# LMS.net
KiCad netlist of a schematic drawn in Altium Designer
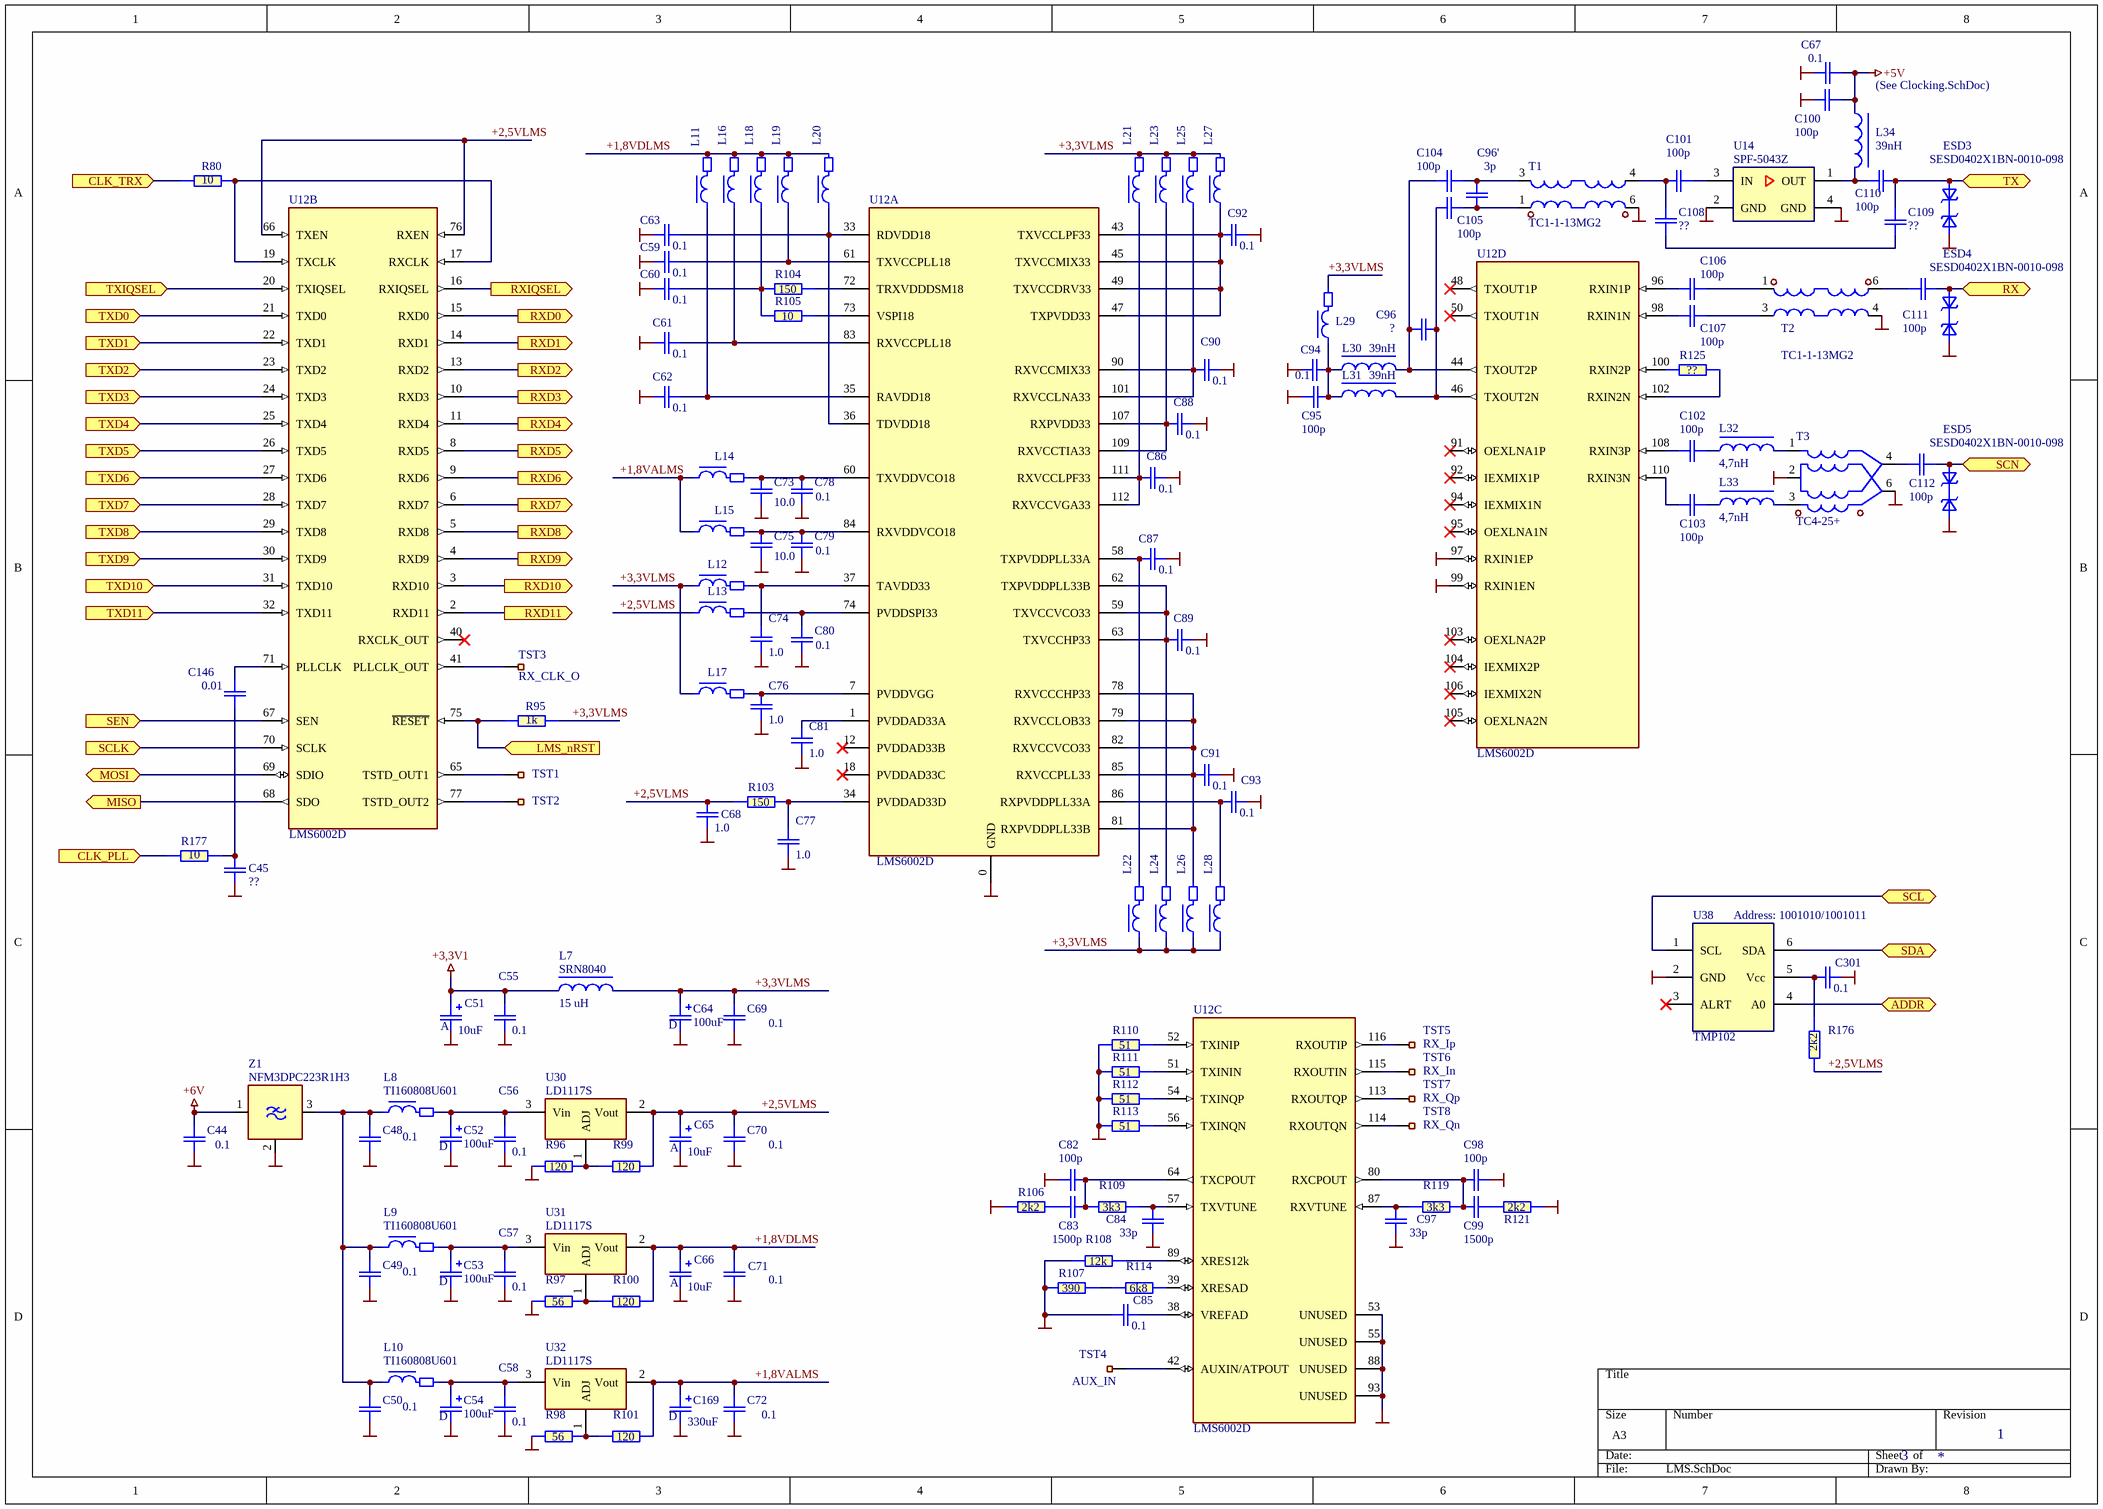
[diagram p0: LMS.SchDoc]

(export (version "E")
  (design (tool "Eeschema 10.0.6"))
  (components
    (comp (ref "C44")
      (value "0.1")
      (footprint "C0402-Phillips")
      (description "Конденсатор")
      (fields (field (name "MANUFACTURER") "MURATA") (field (name "TOLERANCE") "20%"))
      (libsource (lib "Capacitors") (part "C0402"))
    )
    (comp (ref "C45")
      (value "??")
      (footprint "C0603-PHILLIPS")
      (description "Конденсатор")
      (fields (field (name "MANUFACTURER") "MURATA") (field (name "TOLERANCE") "20%"))
      (libsource (lib "altium-import") (part "root_2_mirrored_C0603_"))
    )
    (comp (ref "C48")
      (value "0.1")
      (footprint "C0402-Phillips")
      (description "Конденсатор")
      (fields (field (name "MANUFACTURER") "MURATA") (field (name "TOLERANCE") "20%"))
      (libsource (lib "Capacitors") (part "C0402"))
    )
    (comp (ref "C49")
      (value "0.1")
      (footprint "C0402-Phillips")
      (description "Конденсатор")
      (fields (field (name "MANUFACTURER") "MURATA") (field (name "TOLERANCE") "20%"))
      (libsource (lib "Capacitors") (part "C0402"))
    )
    (comp (ref "C50")
      (value "0.1")
      (footprint "C0402-Phillips")
      (description "Конденсатор")
      (fields (field (name "MANUFACTURER") "MURATA") (field (name "TOLERANCE") "20%"))
      (libsource (lib "Capacitors") (part "C0402"))
    )
    (comp (ref "C51")
      (value "10uF")
      (footprint "CA3216")
      (description "Конденсатор")
      (fields (field (name "MANUFACTURER") "SPRAGUE"))
      (libsource (lib "Capacitors") (part "CA3216"))
    )
    (comp (ref "C52")
      (value "100uF")
      (footprint "cd7343")
      (description "Конденсатор")
      (fields (field (name "MANUFACTURER") "SPRAGUE"))
      (libsource (lib "altium-import") (part "root_0_CD7343_"))
    )
    (comp (ref "C53")
      (value "100uF")
      (footprint "cd7343")
      (description "Конденсатор")
      (fields (field (name "MANUFACTURER") "SPRAGUE"))
      (libsource (lib "altium-import") (part "root_0_CD7343_"))
    )
    (comp (ref "C54")
      (value "100uF")
      (footprint "cd7343")
      (description "Конденсатор")
      (fields (field (name "MANUFACTURER") "SPRAGUE"))
      (libsource (lib "altium-import") (part "root_0_CD7343_"))
    )
    (comp (ref "C55")
      (value "0.1")
      (footprint "C0402-Phillips")
      (description "Конденсатор")
      (fields (field (name "MANUFACTURER") "MURATA") (field (name "TOLERANCE") "20%"))
      (libsource (lib "Capacitors") (part "C0402"))
    )
    (comp (ref "C56")
      (value "0.1")
      (footprint "C0402-Phillips")
      (description "Конденсатор")
      (fields (field (name "MANUFACTURER") "MURATA") (field (name "TOLERANCE") "20%"))
      (libsource (lib "Capacitors") (part "C0402"))
    )
    (comp (ref "C57")
      (value "0.1")
      (footprint "C0402-Phillips")
      (description "Конденсатор")
      (fields (field (name "MANUFACTURER") "MURATA") (field (name "TOLERANCE") "20%"))
      (libsource (lib "Capacitors") (part "C0402"))
    )
    (comp (ref "C58")
      (value "0.1")
      (footprint "C0402-Phillips")
      (description "Конденсатор")
      (fields (field (name "MANUFACTURER") "MURATA") (field (name "TOLERANCE") "20%"))
      (libsource (lib "Capacitors") (part "C0402"))
    )
    (comp (ref "C59")
      (value "0.1")
      (footprint "C0402-Phillips")
      (description "Конденсатор")
      (fields (field (name "MANUFACTURER") "MURATA") (field (name "TOLERANCE") "20%"))
      (libsource (lib "Capacitors") (part "C0402"))
    )
    (comp (ref "C60")
      (value "0.1")
      (footprint "C0402-Phillips")
      (description "Конденсатор")
      (fields (field (name "MANUFACTURER") "MURATA") (field (name "TOLERANCE") "20%"))
      (libsource (lib "Capacitors") (part "C0402"))
    )
    (comp (ref "C61")
      (value "0.1")
      (footprint "C0402-Phillips")
      (description "Конденсатор")
      (fields (field (name "MANUFACTURER") "MURATA") (field (name "TOLERANCE") "20%"))
      (libsource (lib "Capacitors") (part "C0402"))
    )
    (comp (ref "C62")
      (value "0.1")
      (footprint "C0402-Phillips")
      (description "Конденсатор")
      (fields (field (name "MANUFACTURER") "MURATA") (field (name "TOLERANCE") "20%"))
      (libsource (lib "Capacitors") (part "C0402"))
    )
    (comp (ref "C63")
      (value "0.1")
      (footprint "C0402-Phillips")
      (description "Конденсатор")
      (fields (field (name "MANUFACTURER") "MURATA") (field (name "TOLERANCE") "20%"))
      (libsource (lib "Capacitors") (part "C0402"))
    )
    (comp (ref "C64")
      (value "100uF")
      (footprint "cd7343")
      (description "Конденсатор")
      (fields (field (name "MANUFACTURER") "SPRAGUE"))
      (libsource (lib "altium-import") (part "root_0_CD7343_"))
    )
    (comp (ref "C65")
      (value "10uF")
      (footprint "CA3216")
      (description "Конденсатор")
      (fields (field (name "MANUFACTURER") "SPRAGUE"))
      (libsource (lib "Capacitors") (part "CA3216"))
    )
    (comp (ref "C66")
      (value "10uF")
      (footprint "CA3216")
      (description "Конденсатор")
      (fields (field (name "MANUFACTURER") "SPRAGUE"))
      (libsource (lib "Capacitors") (part "CA3216"))
    )
    (comp (ref "C67")
      (value "0.1")
      (footprint "C0402-Phillips")
      (description "Конденсатор")
      (fields (field (name "MANUFACTURER") "MURATA") (field (name "TOLERANCE") "20%"))
      (libsource (lib "Capacitors") (part "C0402"))
    )
    (comp (ref "C68")
      (value "1.0")
      (footprint "C0603-PHILLIPS")
      (description "Конденсатор")
      (fields (field (name "MANUFACTURER") "MURATA") (field (name "TOLERANCE") "20%"))
      (libsource (lib "altium-import") (part "root_0_C0603_"))
    )
    (comp (ref "C69")
      (value "0.1")
      (footprint "C0402-Phillips")
      (description "Конденсатор")
      (fields (field (name "MANUFACTURER") "MURATA") (field (name "TOLERANCE") "20%"))
      (libsource (lib "Capacitors") (part "C0402"))
    )
    (comp (ref "C70")
      (value "0.1")
      (footprint "C0402-Phillips")
      (description "Конденсатор")
      (fields (field (name "MANUFACTURER") "MURATA") (field (name "TOLERANCE") "20%"))
      (libsource (lib "Capacitors") (part "C0402"))
    )
    (comp (ref "C71")
      (value "0.1")
      (footprint "C0402-Phillips")
      (description "Конденсатор")
      (fields (field (name "MANUFACTURER") "MURATA") (field (name "TOLERANCE") "20%"))
      (libsource (lib "Capacitors") (part "C0402"))
    )
    (comp (ref "C72")
      (value "0.1")
      (footprint "C0402-Phillips")
      (description "Конденсатор")
      (fields (field (name "MANUFACTURER") "MURATA") (field (name "TOLERANCE") "20%"))
      (libsource (lib "Capacitors") (part "C0402"))
    )
    (comp (ref "C73")
      (value "10.0")
      (footprint "C0603-Phillips")
      (description "Конденсатор")
      (fields (field (name "MANUFACTURER") "MURATA") (field (name "TOLERANCE") "20%"))
      (libsource (lib "Capacitors") (part "C0603"))
    )
    (comp (ref "C74")
      (value "1.0")
      (footprint "C0603-PHILLIPS")
      (description "Конденсатор")
      (fields (field (name "MANUFACTURER") "MURATA") (field (name "TOLERANCE") "20%"))
      (libsource (lib "altium-import") (part "root_0_C0603_"))
    )
    (comp (ref "C75")
      (value "10.0")
      (footprint "C0603-Phillips")
      (description "Конденсатор")
      (fields (field (name "MANUFACTURER") "MURATA") (field (name "TOLERANCE") "20%"))
      (libsource (lib "Capacitors") (part "C0603"))
    )
    (comp (ref "C76")
      (value "1.0")
      (footprint "C0603-PHILLIPS")
      (description "Конденсатор")
      (fields (field (name "MANUFACTURER") "MURATA") (field (name "TOLERANCE") "20%"))
      (libsource (lib "altium-import") (part "root_0_C0603_"))
    )
    (comp (ref "C77")
      (value "1.0")
      (footprint "C0603-PHILLIPS")
      (description "Конденсатор")
      (fields (field (name "MANUFACTURER") "MURATA") (field (name "TOLERANCE") "20%"))
      (libsource (lib "altium-import") (part "root_0_C0603_"))
    )
    (comp (ref "C78")
      (value "0.1")
      (footprint "C0402-Phillips")
      (description "Конденсатор")
      (fields (field (name "MANUFACTURER") "MURATA") (field (name "TOLERANCE") "20%"))
      (libsource (lib "Capacitors") (part "C0402"))
    )
    (comp (ref "C79")
      (value "0.1")
      (footprint "C0402-cirq")
      (description "Конденсатор")
      (fields (field (name "MANUFACTURER") "MURATA") (field (name "TOLERANCE") "20%"))
      (libsource (lib "Capacitors") (part "C0402"))
    )
    (comp (ref "C80")
      (value "0.1")
      (footprint "C0402-cirq")
      (description "Конденсатор")
      (fields (field (name "MANUFACTURER") "MURATA") (field (name "TOLERANCE") "20%"))
      (libsource (lib "Capacitors") (part "C0402"))
    )
    (comp (ref "C81")
      (value "1.0")
      (footprint "C0603-PHILLIPS")
      (description "Конденсатор")
      (fields (field (name "MANUFACTURER") "MURATA") (field (name "TOLERANCE") "20%"))
      (libsource (lib "altium-import") (part "root_0_C0603_"))
    )
    (comp (ref "C82")
      (value "100p")
      (footprint "C0603-PHILLIPS")
      (description "Конденсатор")
      (fields (field (name "MANUFACTURER") "MURATA") (field (name "TOLERANCE") "20%"))
      (libsource (lib "altium-import") (part "root_1_mirrored_C0603_"))
    )
    (comp (ref "C83")
      (value "1500p")
      (footprint "C0603-PHILLIPS")
      (description "Конденсатор")
      (fields (field (name "MANUFACTURER") "MURATA") (field (name "TOLERANCE") "20%"))
      (libsource (lib "altium-import") (part "root_1_mirrored_C0603_"))
    )
    (comp (ref "C84")
      (value "33p")
      (footprint "C0603-PHILLIPS")
      (description "Конденсатор")
      (fields (field (name "MANUFACTURER") "MURATA") (field (name "TOLERANCE") "20%"))
      (libsource (lib "altium-import") (part "root_2_mirrored_C0603_"))
    )
    (comp (ref "C85")
      (value "0.1")
      (footprint "C0402-Phillips")
      (description "Конденсатор")
      (fields (field (name "MANUFACTURER") "MURATA") (field (name "TOLERANCE") "20%"))
      (libsource (lib "Capacitors") (part "C0402"))
    )
    (comp (ref "C86")
      (value "0.1")
      (footprint "C0402-Phillips")
      (description "Конденсатор")
      (fields (field (name "MANUFACTURER") "MURATA") (field (name "TOLERANCE") "20%"))
      (libsource (lib "Capacitors") (part "C0402"))
    )
    (comp (ref "C87")
      (value "0.1")
      (footprint "C0402-Phillips")
      (description "Конденсатор")
      (fields (field (name "MANUFACTURER") "MURATA") (field (name "TOLERANCE") "20%"))
      (libsource (lib "Capacitors") (part "C0402"))
    )
    (comp (ref "C88")
      (value "0.1")
      (footprint "C0402-cirq")
      (description "Конденсатор")
      (fields (field (name "MANUFACTURER") "MURATA") (field (name "TOLERANCE") "20%"))
      (libsource (lib "Capacitors") (part "C0402"))
    )
    (comp (ref "C89")
      (value "0.1")
      (footprint "C0402-cirq")
      (description "Конденсатор")
      (fields (field (name "MANUFACTURER") "MURATA") (field (name "TOLERANCE") "20%"))
      (libsource (lib "Capacitors") (part "C0402"))
    )
    (comp (ref "C90")
      (value "0.1")
      (footprint "C0402-Phillips")
      (description "Конденсатор")
      (fields (field (name "MANUFACTURER") "MURATA") (field (name "TOLERANCE") "20%"))
      (libsource (lib "Capacitors") (part "C0402"))
    )
    (comp (ref "C91")
      (value "0.1")
      (footprint "C0402-Phillips")
      (description "Конденсатор")
      (fields (field (name "MANUFACTURER") "MURATA") (field (name "TOLERANCE") "20%"))
      (libsource (lib "Capacitors") (part "C0402"))
    )
    (comp (ref "C92")
      (value "0.1")
      (footprint "C0402-cirq")
      (description "Конденсатор")
      (fields (field (name "MANUFACTURER") "MURATA") (field (name "TOLERANCE") "20%"))
      (libsource (lib "Capacitors") (part "C0402"))
    )
    (comp (ref "C93")
      (value "0.1")
      (footprint "C0402-Phillips")
      (description "Конденсатор")
      (fields (field (name "MANUFACTURER") "MURATA") (field (name "TOLERANCE") "20%"))
      (libsource (lib "Capacitors") (part "C0402"))
    )
    (comp (ref "C94")
      (value "0.1")
      (footprint "C0402-Phillips")
      (description "Конденсатор")
      (fields (field (name "MANUFACTURER") "MURATA") (field (name "TOLERANCE") "20%"))
      (libsource (lib "Capacitors") (part "C0402"))
    )
    (comp (ref "C95")
      (value "100p")
      (footprint "C0603-PHILLIPS")
      (description "Конденсатор")
      (fields (field (name "MANUFACTURER") "MURATA") (field (name "TOLERANCE") "20%"))
      (libsource (lib "altium-import") (part "root_3_C0603_"))
    )
    (comp (ref "C96")
      (value "?")
      (footprint "C0603-PHILLIPS")
      (description "Конденсатор")
      (fields (field (name "MANUFACTURER") "MURATA") (field (name "TOLERANCE") "20%"))
      (libsource (lib "altium-import") (part "root_3_C0603_"))
    )
    (comp (ref "C96'")
      (value "3p")
      (footprint "C0603-PHILLIPS")
      (description "Конденсатор")
      (fields (field (name "MANUFACTURER") "MURATA") (field (name "TOLERANCE") "20%"))
      (libsource (lib "altium-import") (part "root_2_C0603_"))
    )
    (comp (ref "C97")
      (value "33p")
      (footprint "C0603-PHILLIPS")
      (description "Конденсатор")
      (fields (field (name "MANUFACTURER") "MURATA") (field (name "TOLERANCE") "20%"))
      (libsource (lib "altium-import") (part "root_2_C0603_"))
    )
    (comp (ref "C98")
      (value "100p")
      (footprint "C0603-PHILLIPS")
      (description "Конденсатор")
      (fields (field (name "MANUFACTURER") "MURATA") (field (name "TOLERANCE") "20%"))
      (libsource (lib "altium-import") (part "root_1_C0603_"))
    )
    (comp (ref "C99")
      (value "1500p")
      (footprint "C0603-PHILLIPS")
      (description "Конденсатор")
      (fields (field (name "MANUFACTURER") "MURATA") (field (name "TOLERANCE") "20%"))
      (libsource (lib "altium-import") (part "root_1_C0603_"))
    )
    (comp (ref "C100")
      (value "100p")
      (footprint "C0603-PHILLIPS")
      (description "Конденсатор")
      (fields (field (name "MANUFACTURER") "MURATA") (field (name "TOLERANCE") "20%"))
      (libsource (lib "altium-import") (part "root_1_C0603_"))
    )
    (comp (ref "C101")
      (value "100p")
      (footprint "C0603-PHILLIPS")
      (description "Конденсатор")
      (fields (field (name "MANUFACTURER") "MURATA") (field (name "TOLERANCE") "20%"))
      (libsource (lib "altium-import") (part "root_1_C0603_"))
    )
    (comp (ref "C102")
      (value "100p")
      (footprint "C0603-PHILLIPS")
      (description "Конденсатор")
      (fields (field (name "MANUFACTURER") "MURATA") (field (name "TOLERANCE") "20%"))
      (libsource (lib "altium-import") (part "root_1_C0603_"))
    )
    (comp (ref "C103")
      (value "100p")
      (footprint "C0603-PHILLIPS")
      (description "Конденсатор")
      (fields (field (name "MANUFACTURER") "MURATA") (field (name "TOLERANCE") "20%"))
      (libsource (lib "altium-import") (part "root_1_C0603_"))
    )
    (comp (ref "C104")
      (value "100p")
      (footprint "C0603-PHILLIPS")
      (description "Конденсатор")
      (fields (field (name "MANUFACTURER") "MURATA") (field (name "TOLERANCE") "20%"))
      (libsource (lib "altium-import") (part "root_1_C0603_"))
    )
    (comp (ref "C105")
      (value "100p")
      (footprint "C0603-PHILLIPS")
      (description "Конденсатор")
      (fields (field (name "MANUFACTURER") "MURATA") (field (name "TOLERANCE") "20%"))
      (libsource (lib "altium-import") (part "root_1_C0603_"))
    )
    (comp (ref "C106")
      (value "100p")
      (footprint "C0603-PHILLIPS")
      (description "Конденсатор")
      (fields (field (name "MANUFACTURER") "MURATA") (field (name "TOLERANCE") "20%"))
      (libsource (lib "altium-import") (part "root_1_C0603_"))
    )
    (comp (ref "C107")
      (value "100p")
      (footprint "C0603-PHILLIPS")
      (description "Конденсатор")
      (fields (field (name "MANUFACTURER") "MURATA") (field (name "TOLERANCE") "20%"))
      (libsource (lib "altium-import") (part "root_1_C0603_"))
    )
    (comp (ref "C108")
      (value "??")
      (footprint "C0603-PHILLIPS")
      (description "Конденсатор")
      (fields (field (name "MANUFACTURER") "MURATA") (field (name "TOLERANCE") "20%"))
      (libsource (lib "altium-import") (part "root_0_C0603_"))
    )
    (comp (ref "C109")
      (value "??")
      (footprint "C0603-PHILLIPS")
      (description "Конденсатор")
      (fields (field (name "MANUFACTURER") "MURATA") (field (name "TOLERANCE") "20%"))
      (libsource (lib "altium-import") (part "root_2_C0603_"))
    )
    (comp (ref "C110")
      (value "100p")
      (footprint "C0603-PHILLIPS")
      (description "Конденсатор")
      (fields (field (name "MANUFACTURER") "MURATA") (field (name "TOLERANCE") "20%"))
      (libsource (lib "altium-import") (part "root_1_C0603_"))
    )
    (comp (ref "C111")
      (value "100p")
      (footprint "C0603-PHILLIPS")
      (description "Конденсатор")
      (fields (field (name "MANUFACTURER") "MURATA") (field (name "TOLERANCE") "20%"))
      (libsource (lib "altium-import") (part "root_3_C0603_"))
    )
    (comp (ref "C112")
      (value "100p")
      (footprint "C0603-PHILLIPS")
      (description "Конденсатор")
      (fields (field (name "MANUFACTURER") "MURATA") (field (name "TOLERANCE") "20%"))
      (libsource (lib "altium-import") (part "root_1_C0603_"))
    )
    (comp (ref "C146")
      (value "0.01")
      (footprint "C0402-Phillips")
      (description "Конденсатор")
      (fields (field (name "MANUFACTURER") "MURATA") (field (name "TOLERANCE") "20%"))
      (libsource (lib "Capacitors") (part "C0402"))
    )
    (comp (ref "C169")
      (value "330uF")
      (footprint "cd7343")
      (description "Конденсатор")
      (fields (field (name "MANUFACTURER") "Kemet"))
      (libsource (lib "altium-import") (part "root_0_CD7343_"))
    )
    (comp (ref "C301")
      (value "0.1")
      (footprint "C0402-Phillips")
      (description "Конденсатор")
      (fields (field (name "MANUFACTURER") "MURATA") (field (name "TOLERANCE") "20%"))
      (libsource (lib "Capacitors") (part "C0402"))
    )
    (comp (ref "ESD3")
      (value "SESD0402X1BN-0010-098")
      (footprint "R0402-Phillips")
      (description "ESD diod bi-directional")
      (fields (field (name "MANUFACTURER") "Tyco Electronics Corp"))
      (libsource (lib "*") (part "SESD0402X"))
    )
    (comp (ref "ESD4")
      (value "SESD0402X1BN-0010-098")
      (footprint "R0402-Phillips")
      (description "ESD diod bi-directional")
      (fields (field (name "MANUFACTURER") "Tyco Electronics Corp"))
      (libsource (lib "*") (part "SESD0402X"))
    )
    (comp (ref "ESD5")
      (value "SESD0402X1BN-0010-098")
      (footprint "R0402-Phillips")
      (description "ESD diod bi-directional")
      (fields (field (name "MANUFACTURER") "Tyco Electronics Corp"))
      (libsource (lib "*") (part "SESD0402X"))
    )
    (comp (ref "L7")
      (value "15 uH")
      (footprint "SRN8040")
      (description "Индуктивность")
      (fields (field (name "MANUFACTURER") "BOURNS") (field (name "NAME") "SRN8040"))
      (libsource (lib "Andy") (part "L-SRN8040"))
    )
    (comp (ref "L8")
      (value "TI160808U601")
      (footprint "Andy:Ti160808-Phillips")
      (description "Дроссель ЭМС")
      (fields (field (name "MANUFACTURER") "MURATA"))
      (libsource (lib "altium-import") (part "root_0_TI160808_"))
    )
    (comp (ref "L9")
      (value "TI160808U601")
      (footprint "Andy:Ti160808-Phillips")
      (description "Дроссель ЭМС")
      (fields (field (name "MANUFACTURER") "MURATA"))
      (libsource (lib "altium-import") (part "root_0_TI160808_"))
    )
    (comp (ref "L10")
      (value "TI160808U601")
      (footprint "Andy:Ti160808-Phillips")
      (description "Дроссель ЭМС")
      (fields (field (name "MANUFACTURER") "MURATA"))
      (libsource (lib "altium-import") (part "root_0_TI160808_"))
    )
    (comp (ref "L11")
      (value "TI160808U601")
      (footprint "Andy:Ti160808-Phillips")
      (description "Дроссель ЭМС")
      (fields (field (name "MANUFACTURER") "MURATA"))
      (libsource (lib "altium-import") (part "root_1_TI160808_"))
    )
    (comp (ref "L12")
      (value "TI160808U601")
      (footprint "Andy:Ti160808-Phillips")
      (description "Дроссель ЭМС")
      (fields (field (name "MANUFACTURER") "MURATA"))
      (libsource (lib "altium-import") (part "root_0_TI160808_"))
    )
    (comp (ref "L13")
      (value "TI160808U601")
      (footprint "Andy:Ti160808-Phillips")
      (description "Дроссель ЭМС")
      (fields (field (name "MANUFACTURER") "MURATA"))
      (libsource (lib "altium-import") (part "root_0_TI160808_"))
    )
    (comp (ref "L14")
      (value "TI160808U601")
      (footprint "Andy:Ti160808-Phillips")
      (description "Дроссель ЭМС")
      (fields (field (name "MANUFACTURER") "MURATA"))
      (libsource (lib "altium-import") (part "root_0_TI160808_"))
    )
    (comp (ref "L15")
      (value "TI160808U601")
      (footprint "Andy:Ti160808-Phillips")
      (description "Дроссель ЭМС")
      (fields (field (name "MANUFACTURER") "MURATA"))
      (libsource (lib "altium-import") (part "root_0_TI160808_"))
    )
    (comp (ref "L16")
      (value "TI160808U601")
      (footprint "Andy:Ti160808-Phillips")
      (description "Дроссель ЭМС")
      (fields (field (name "MANUFACTURER") "MURATA"))
      (libsource (lib "altium-import") (part "root_1_TI160808_"))
    )
    (comp (ref "L17")
      (value "TI160808U601")
      (footprint "Andy:Ti160808-Phillips")
      (description "Дроссель ЭМС")
      (fields (field (name "MANUFACTURER") "MURATA"))
      (libsource (lib "altium-import") (part "root_0_TI160808_"))
    )
    (comp (ref "L18")
      (value "TI160808U601")
      (footprint "Andy:Ti160808-Phillips")
      (description "Дроссель ЭМС")
      (fields (field (name "MANUFACTURER") "MURATA"))
      (libsource (lib "altium-import") (part "root_1_TI160808_"))
    )
    (comp (ref "L19")
      (value "TI160808U601")
      (footprint "Andy:Ti160808-Phillips")
      (description "Дроссель ЭМС")
      (fields (field (name "MANUFACTURER") "MURATA"))
      (libsource (lib "altium-import") (part "root_1_TI160808_"))
    )
    (comp (ref "L20")
      (value "TI160808U601")
      (footprint "Andy:Ti160808-Phillips")
      (description "Дроссель ЭМС")
      (fields (field (name "MANUFACTURER") "MURATA"))
      (libsource (lib "altium-import") (part "root_1_TI160808_"))
    )
    (comp (ref "L21")
      (value "TI160808U601")
      (footprint "Andy:Ti160808-Phillips")
      (description "Дроссель ЭМС")
      (fields (field (name "MANUFACTURER") "MURATA"))
      (libsource (lib "altium-import") (part "root_1_TI160808_"))
    )
    (comp (ref "L22")
      (value "TI160808U601")
      (footprint "Andy:Ti160808-Phillips")
      (description "Дроссель ЭМС")
      (fields (field (name "MANUFACTURER") "MURATA"))
      (libsource (lib "altium-import") (part "root_1_TI160808_"))
    )
    (comp (ref "L23")
      (value "TI160808U601")
      (footprint "Andy:Ti160808-Phillips")
      (description "Дроссель ЭМС")
      (fields (field (name "MANUFACTURER") "MURATA"))
      (libsource (lib "altium-import") (part "root_1_TI160808_"))
    )
    (comp (ref "L24")
      (value "TI160808U601")
      (footprint "Andy:Ti160808-Phillips")
      (description "Дроссель ЭМС")
      (fields (field (name "MANUFACTURER") "MURATA"))
      (libsource (lib "altium-import") (part "root_1_TI160808_"))
    )
    (comp (ref "L25")
      (value "TI160808U601")
      (footprint "Andy:Ti160808-Phillips")
      (description "Дроссель ЭМС")
      (fields (field (name "MANUFACTURER") "MURATA"))
      (libsource (lib "altium-import") (part "root_1_TI160808_"))
    )
    (comp (ref "L26")
      (value "TI160808U601")
      (footprint "Andy:Ti160808-Phillips")
      (description "Дроссель ЭМС")
      (fields (field (name "MANUFACTURER") "MURATA"))
      (libsource (lib "altium-import") (part "root_1_TI160808_"))
    )
    (comp (ref "L27")
      (value "TI160808U601")
      (footprint "Andy:Ti160808-Phillips")
      (description "Дроссель ЭМС")
      (fields (field (name "MANUFACTURER") "MURATA"))
      (libsource (lib "altium-import") (part "root_1_TI160808_"))
    )
    (comp (ref "L28")
      (value "TI160808U601")
      (footprint "Andy:Ti160808-Phillips")
      (description "Дроссель ЭМС")
      (fields (field (name "MANUFACTURER") "MURATA"))
      (libsource (lib "altium-import") (part "root_1_TI160808_"))
    )
    (comp (ref "L29")
      (value "TI160808U601")
      (footprint "Andy:Ti160808-Phillips")
      (description "Дроссель ЭМС")
      (fields (field (name "MANUFACTURER") "MURATA"))
      (libsource (lib "altium-import") (part "root_1_TI160808_"))
    )
    (comp (ref "L30")
      (value "39nH")
      (footprint "Andy:TF160808-Phillips")
      (description "Индуктивность")
      (fields (field (name "MANUFACTURER") "SMD"))
      (libsource (lib "altium-import") (part "root_0_TF160808_"))
    )
    (comp (ref "L31")
      (value "39nH")
      (footprint "Andy:TF160808-Phillips")
      (description "Индуктивность")
      (fields (field (name "MANUFACTURER") "SMD"))
      (libsource (lib "altium-import") (part "root_0_TF160808_"))
    )
    (comp (ref "L32")
      (value "4,7nH")
      (footprint "Andy:TF160808-Phillips")
      (description "Индуктивность")
      (fields (field (name "MANUFACTURER") "SMD"))
      (libsource (lib "altium-import") (part "root_0_TF160808_"))
    )
    (comp (ref "L33")
      (value "4,7nH")
      (footprint "Andy:TF160808-Phillips")
      (description "Индуктивность")
      (fields (field (name "MANUFACTURER") "SMD"))
      (libsource (lib "altium-import") (part "root_0_TF160808_"))
    )
    (comp (ref "L34")
      (value "39nH")
      (footprint "Andy:TF160808-Phillips")
      (description "Индуктивность")
      (fields (field (name "MANUFACTURER") "SMD"))
      (libsource (lib "altium-import") (part "root_3_TF160808_"))
    )
    (comp (ref "R80")
      (value "10")
      (footprint "R0603-PHILLIPS")
      (description "Резистор")
      (fields (field (name "MANUFACTURER") "YAGEO") (field (name "TOLERANCE") "5%"))
      (libsource (lib "altium-import") (part "root_1_R0603_"))
    )
    (comp (ref "R95")
      (value "1k")
      (footprint "R0603-PHILLIPS")
      (description "Резистор")
      (fields (field (name "MANUFACTURER") "YAGEO") (field (name "TOLERANCE") "5%"))
      (libsource (lib "altium-import") (part "root_1_R0603_"))
    )
    (comp (ref "R96")
      (value "120")
      (footprint "R0603-PHILLIPS")
      (description "Резистор")
      (fields (field (name "MANUFACTURER") "YAGEO") (field (name "TOLERANCE") "5%"))
      (libsource (lib "altium-import") (part "root_1_R0603_"))
    )
    (comp (ref "R97")
      (value "56")
      (footprint "R0603-PHILLIPS")
      (description "Резистор")
      (fields (field (name "MANUFACTURER") "YAGEO") (field (name "TOLERANCE") "5%"))
      (libsource (lib "altium-import") (part "root_1_R0603_"))
    )
    (comp (ref "R98")
      (value "56")
      (footprint "R0603-PHILLIPS")
      (description "Резистор")
      (fields (field (name "MANUFACTURER") "YAGEO") (field (name "TOLERANCE") "5%"))
      (libsource (lib "altium-import") (part "root_1_R0603_"))
    )
    (comp (ref "R99")
      (value "120")
      (footprint "R0603-PHILLIPS")
      (description "Резистор")
      (fields (field (name "MANUFACTURER") "YAGEO") (field (name "TOLERANCE") "5%"))
      (libsource (lib "altium-import") (part "root_1_R0603_"))
    )
    (comp (ref "R100")
      (value "120")
      (footprint "R0603-PHILLIPS")
      (description "Резистор")
      (fields (field (name "MANUFACTURER") "YAGEO") (field (name "TOLERANCE") "5%"))
      (libsource (lib "altium-import") (part "root_1_R0603_"))
    )
    (comp (ref "R101")
      (value "120")
      (footprint "R0603-PHILLIPS")
      (description "Резистор")
      (fields (field (name "MANUFACTURER") "YAGEO") (field (name "TOLERANCE") "5%"))
      (libsource (lib "altium-import") (part "root_1_R0603_"))
    )
    (comp (ref "R103")
      (value "150")
      (footprint "R0603-PHILLIPS")
      (description "Резистор")
      (fields (field (name "MANUFACTURER") "YAGEO") (field (name "TOLERANCE") "5%"))
      (libsource (lib "altium-import") (part "root_1_R0603_"))
    )
    (comp (ref "R104")
      (value "150")
      (footprint "R0603-PHILLIPS")
      (description "Резистор")
      (fields (field (name "MANUFACTURER") "YAGEO") (field (name "TOLERANCE") "5%"))
      (libsource (lib "altium-import") (part "root_1_R0603_"))
    )
    (comp (ref "R105")
      (value "10")
      (footprint "R0603-PHILLIPS")
      (description "Резистор")
      (fields (field (name "MANUFACTURER") "YAGEO") (field (name "TOLERANCE") "5%"))
      (libsource (lib "altium-import") (part "root_1_R0603_"))
    )
    (comp (ref "R106")
      (value "2k2")
      (footprint "R0603-PHILLIPS")
      (description "Резистор")
      (fields (field (name "MANUFACTURER") "YAGEO") (field (name "TOLERANCE") "5%"))
      (libsource (lib "altium-import") (part "root_1_R0603_"))
    )
    (comp (ref "R107")
      (value "390")
      (footprint "R0603-PHILLIPS")
      (description "Резистор")
      (fields (field (name "MANUFACTURER") "YAGEO") (field (name "TOLERANCE") "5%"))
      (libsource (lib "altium-import") (part "root_1_R0603_"))
    )
    (comp (ref "R108")
      (value "12k")
      (footprint "R0603-PHILLIPS")
      (description "Резистор")
      (fields (field (name "MANUFACTURER") "YAGEO") (field (name "TOLERANCE") "5%"))
      (libsource (lib "altium-import") (part "root_1_R0603_"))
    )
    (comp (ref "R109")
      (value "3k3")
      (footprint "R0603-PHILLIPS")
      (description "Резистор")
      (fields (field (name "MANUFACTURER") "YAGEO") (field (name "TOLERANCE") "5%"))
      (libsource (lib "altium-import") (part "root_1_R0603_"))
    )
    (comp (ref "R110")
      (value "51")
      (footprint "R0603-PHILLIPS")
      (description "Резистор")
      (fields (field (name "MANUFACTURER") "YAGEO") (field (name "TOLERANCE") "5%"))
      (libsource (lib "altium-import") (part "root_1_R0603_"))
    )
    (comp (ref "R111")
      (value "51")
      (footprint "R0603-PHILLIPS")
      (description "Резистор")
      (fields (field (name "MANUFACTURER") "YAGEO") (field (name "TOLERANCE") "5%"))
      (libsource (lib "altium-import") (part "root_1_R0603_"))
    )
    (comp (ref "R112")
      (value "51")
      (footprint "R0603-PHILLIPS")
      (description "Резистор")
      (fields (field (name "MANUFACTURER") "YAGEO") (field (name "TOLERANCE") "5%"))
      (libsource (lib "altium-import") (part "root_1_R0603_"))
    )
    (comp (ref "R113")
      (value "51")
      (footprint "R0603-PHILLIPS")
      (description "Резистор")
      (fields (field (name "MANUFACTURER") "YAGEO") (field (name "TOLERANCE") "5%"))
      (libsource (lib "altium-import") (part "root_1_R0603_"))
    )
    (comp (ref "R114")
      (value "6k8")
      (footprint "R0603-PHILLIPS")
      (description "Резистор")
      (fields (field (name "MANUFACTURER") "YAGEO") (field (name "TOLERANCE") "5%"))
      (libsource (lib "altium-import") (part "root_1_R0603_"))
    )
    (comp (ref "R119")
      (value "3k3")
      (footprint "R0603-PHILLIPS")
      (description "Резистор")
      (fields (field (name "MANUFACTURER") "YAGEO") (field (name "TOLERANCE") "5%"))
      (libsource (lib "altium-import") (part "root_1_R0603_"))
    )
    (comp (ref "R121")
      (value "2k2")
      (footprint "R0603-PHILLIPS")
      (description "Резистор")
      (fields (field (name "MANUFACTURER") "YAGEO") (field (name "TOLERANCE") "5%"))
      (libsource (lib "altium-import") (part "root_1_R0603_"))
    )
    (comp (ref "R125")
      (value "??")
      (footprint "R0603-PHILLIPS")
      (description "Резистор")
      (fields (field (name "MANUFACTURER") "YAGEO") (field (name "TOLERANCE") "5%"))
      (libsource (lib "altium-import") (part "root_1_R0603_"))
    )
    (comp (ref "R176")
      (value "2k2")
      (footprint "R0603-PHILLIPS")
      (description "Резистор")
      (fields (field (name "MANUFACTURER") "YAGEO") (field (name "TOLERANCE") "5%"))
      (libsource (lib "altium-import") (part "root_2_R0603_"))
    )
    (comp (ref "R177")
      (value "10")
      (footprint "R0603-PHILLIPS")
      (description "Резистор")
      (fields (field (name "MANUFACTURER") "YAGEO") (field (name "TOLERANCE") "5%"))
      (libsource (lib "altium-import") (part "root_1_R0603_"))
    )
    (comp (ref "T1")
      (value "TC1-1-13MG2")
      (footprint "AT224-1")
      (description "Трансформатор")
      (fields (field (name "MANUFACTURER") "Mini-Cirquits"))
      (libsource (lib "") (part "TC1-1-13_1"))
    )
    (comp (ref "T2")
      (value "TC1-1-13MG2")
      (footprint "AT224-1")
      (description "Трансформатор")
      (fields (field (name "MANUFACTURER") "Mini-Cirquits"))
      (libsource (lib "Inductance Transformers") (part "TC1-1-13"))
    )
    (comp (ref "T3")
      (value "TC4-25+")
      (footprint "AT224-1")
      (description "Трансформатор")
      (fields (field (name "MANUFACTURER") "Mini-Cirquits"))
      (libsource (lib "Inductance Transformers") (part "TC4-25"))
    )
    (comp (ref "TST1")
      (value "~")
      (footprint "kp40x40")
      (description "Контактна  площадка")
      (fields (field (name "MANUFACTURER") "Конструктив"))
      (libsource (lib "") (part "KP_1"))
    )
    (comp (ref "TST2")
      (value "~")
      (footprint "kp40x40")
      (description "Контактна  площадка")
      (fields (field (name "MANUFACTURER") "Конструктив"))
      (libsource (lib "") (part "KP_1"))
    )
    (comp (ref "TST3")
      (value "RX_CLK_O")
      (footprint "kp40x40")
      (description "Контактна  площадка")
      (fields (field (name "MANUFACTURER") "Конструктив"))
      (libsource (lib "") (part "KP_1"))
    )
    (comp (ref "TST4")
      (value "AUX_IN")
      (footprint "kp40x40")
      (description "Контактна  площадка")
      (fields (field (name "MANUFACTURER") "Конструктив"))
      (libsource (lib "Connectors") (part "KP"))
    )
    (comp (ref "TST5")
      (value "RX_Ip")
      (footprint "kp40x40")
      (description "Контактна  площадка")
      (fields (field (name "MANUFACTURER") "Конструктив"))
      (libsource (lib "") (part "KP_1"))
    )
    (comp (ref "TST6")
      (value "RX_In")
      (footprint "kp40x40")
      (description "Контактна  площадка")
      (fields (field (name "MANUFACTURER") "Конструктив"))
      (libsource (lib "") (part "KP_1"))
    )
    (comp (ref "TST7")
      (value "RX_Qp")
      (footprint "kp40x40")
      (description "Контактна  площадка")
      (fields (field (name "MANUFACTURER") "Конструктив"))
      (libsource (lib "") (part "KP_1"))
    )
    (comp (ref "TST8")
      (value "RX_Qn")
      (footprint "kp40x40")
      (description "Контактна  площадка")
      (fields (field (name "MANUFACTURER") "Конструктив"))
      (libsource (lib "") (part "KP_1"))
    )
    (comp (ref "U12")
      (value "LMS6002D")
      (footprint "DQFN120(9x9/0.5mm)")
      (description "Микросхема")
      (fields (field (name "MANUFACTURER") "Lime Microsystems"))
      (libsource (lib "Andy") (part "LMS6002D"))
    )
    (comp (ref "U14")
      (value "SPF-5043Z")
      (footprint "SOT-343[2X1.25]")
      (description "Микросхема")
      (fields (field (name "MANUFACTURER") "RFMD"))
      (libsource (lib "MicroCircuitsM-Z") (part "SPF-5043Z"))
    )
    (comp (ref "U30")
      (value "LD1117S")
      (footprint "Foot3-4pins:SOT-223-1")
      (description "Микросхема")
      (fields (field (name "MANUFACTURER") "STMicro"))
      (libsource (lib "altium-import") (part "root_0_LD1117ADJ_"))
    )
    (comp (ref "U31")
      (value "LD1117S")
      (footprint "Foot3-4pins:SOT-223-1")
      (description "Микросхема")
      (fields (field (name "MANUFACTURER") "STMicro"))
      (libsource (lib "altium-import") (part "root_0_LD1117ADJ_"))
    )
    (comp (ref "U32")
      (value "LD1117S")
      (footprint "Foot3-4pins:SOT-223-1")
      (description "Микросхема")
      (fields (field (name "MANUFACTURER") "STMicro"))
      (libsource (lib "altium-import") (part "root_0_LD1117ADJ_"))
    )
    (comp (ref "U38")
      (value "TMP102")
      (footprint "PDSO-G6")
      (description "IC temperature sensor I2C")
      (fields (field (name "MANUFACTURER") "TI") (field (name "ADDRESS") "1001010/1001011"))
      (libsource (lib "Andy") (part "TMP102"))
    )
    (comp (ref "Z1")
      (value "NFM3DPC223R1H3")
      (footprint "NFM3DP")
      (description "Фильтр")
      (fields (field (name "MANUFACTURER") "Murata"))
      (libsource (lib "altium-import") (part "root_0_NFM3DP_"))
    )
  )
  (nets
    (net (code "1") (name "+3,3V1") (class "Default")
      (node (ref "C51") (pin "1") (pinfunction "+_1") (pintype "passive"))
      (node (ref "C55") (pin "1") (pinfunction "1_1") (pintype "passive"))
      (node (ref "L7") (pin "1") (pinfunction "1_1") (pintype "passive"))
    )
    (net (code "2") (name "+5V") (class "Default")
      (node (ref "C100") (pin "2") (pinfunction "2_2") (pintype "passive"))
      (node (ref "C67") (pin "2") (pinfunction "2_2") (pintype "passive"))
      (node (ref "L34") (pin "1") (pinfunction "1_1") (pintype "passive"))
    )
    (net (code "3") (name "+6V") (class "Default")
      (node (ref "C44") (pin "1") (pinfunction "1_1") (pintype "passive"))
      (node (ref "Z1") (pin "1") (pinfunction "1_1") (pintype "passive"))
    )
    (net (code "4") (name "/+1,8VALMS") (class "Default")
      (node (ref "C169") (pin "1") (pinfunction "+_1") (pintype "passive"))
      (node (ref "C72") (pin "1") (pinfunction "1_1") (pintype "passive"))
      (node (ref "L14") (pin "1") (pinfunction "1_1") (pintype "passive"))
      (node (ref "L15") (pin "1") (pinfunction "1_1") (pintype "passive"))
      (node (ref "R101") (pin "2") (pinfunction "2_2") (pintype "passive"))
      (node (ref "U32") (pin "2") (pinfunction "Vout_2") (pintype "passive"))
    )
    (net (code "5") (name "/+1,8VDLMS") (class "Default")
      (node (ref "C66") (pin "1") (pinfunction "+_1") (pintype "passive"))
      (node (ref "C71") (pin "1") (pinfunction "1_1") (pintype "passive"))
      (node (ref "L11") (pin "2") (pinfunction "2_2") (pintype "passive"))
      (node (ref "L16") (pin "2") (pinfunction "2_2") (pintype "passive"))
      (node (ref "L18") (pin "2") (pinfunction "2_2") (pintype "passive"))
      (node (ref "L19") (pin "2") (pinfunction "2_2") (pintype "passive"))
      (node (ref "L20") (pin "2") (pinfunction "2_2") (pintype "passive"))
      (node (ref "R100") (pin "2") (pinfunction "2_2") (pintype "passive"))
      (node (ref "U31") (pin "2") (pinfunction "Vout_2") (pintype "passive"))
    )
    (net (code "6") (name "/+2,5VLMS") (class "Default")
      (node (ref "C65") (pin "1") (pinfunction "+_1") (pintype "passive"))
      (node (ref "C68") (pin "1") (pinfunction "1_1") (pintype "passive"))
      (node (ref "C70") (pin "1") (pinfunction "1_1") (pintype "passive"))
      (node (ref "L13") (pin "1") (pinfunction "1_1") (pintype "passive"))
      (node (ref "R103") (pin "1") (pinfunction "1_1") (pintype "passive"))
      (node (ref "R176") (pin "1") (pinfunction "1_1") (pintype "passive"))
      (node (ref "R99") (pin "2") (pinfunction "2_2") (pintype "passive"))
      (node (ref "U12") (pin "66") (pinfunction "TXEN_66") (pintype "input"))
      (node (ref "U12") (pin "76") (pinfunction "RXEN_76") (pintype "input"))
      (node (ref "U30") (pin "2") (pinfunction "Vout_2") (pintype "passive"))
    )
    (net (code "7") (name "/+3,3VLMS") (class "Default")
      (node (ref "C64") (pin "1") (pinfunction "+_1") (pintype "passive"))
      (node (ref "C69") (pin "1") (pinfunction "1_1") (pintype "passive"))
      (node (ref "L12") (pin "1") (pinfunction "1_1") (pintype "passive"))
      (node (ref "L17") (pin "1") (pinfunction "1_1") (pintype "passive"))
      (node (ref "L21") (pin "2") (pinfunction "2_2") (pintype "passive"))
      (node (ref "L22") (pin "1") (pinfunction "1_1") (pintype "passive"))
      (node (ref "L23") (pin "2") (pinfunction "2_2") (pintype "passive"))
      (node (ref "L24") (pin "1") (pinfunction "1_1") (pintype "passive"))
      (node (ref "L25") (pin "2") (pinfunction "2_2") (pintype "passive"))
      (node (ref "L26") (pin "1") (pinfunction "1_1") (pintype "passive"))
      (node (ref "L27") (pin "2") (pinfunction "2_2") (pintype "passive"))
      (node (ref "L28") (pin "1") (pinfunction "1_1") (pintype "passive"))
      (node (ref "L29") (pin "2") (pinfunction "2_2") (pintype "passive"))
      (node (ref "L7") (pin "2") (pinfunction "2_2") (pintype "passive"))
      (node (ref "R95") (pin "2") (pinfunction "2_2") (pintype "passive"))
    )
    (net (code "8") (name "/ADDR") (class "Default")
      (node (ref "U38") (pin "4") (pinfunction "A0_4") (pintype "passive"))
    )
    (net (code "9") (name "/CLK_PLL") (class "Default")
      (node (ref "R177") (pin "1") (pinfunction "1_1") (pintype "passive"))
    )
    (net (code "10") (name "/CLK_TRX") (class "Default")
      (node (ref "R80") (pin "1") (pinfunction "1_1") (pintype "passive"))
    )
    (net (code "11") (name "/LMS_nRST") (class "Default")
      (node (ref "R95") (pin "1") (pinfunction "1_1") (pintype "passive"))
      (node (ref "U12") (pin "75") (pinfunction "~{RESET}_75") (pintype "input"))
    )
    (net (code "12") (name "/MISO") (class "Default")
      (node (ref "U12") (pin "68") (pinfunction "SDO_68") (pintype "output"))
    )
    (net (code "13") (name "/MOSI") (class "Default")
      (node (ref "U12") (pin "69") (pinfunction "SDIO_69") (pintype "bidirectional"))
    )
    (net (code "14") (name "/RX") (class "Default")
      (node (ref "C111") (pin "1") (pinfunction "1_1") (pintype "passive"))
      (node (ref "ESD4") (pin "2") (pinfunction "A2_2") (pintype "passive"))
    )
    (net (code "15") (name "/RXD0") (class "Default")
      (node (ref "U12") (pin "15") (pinfunction "RXD0_15") (pintype "output"))
    )
    (net (code "16") (name "/RXD1") (class "Default")
      (node (ref "U12") (pin "14") (pinfunction "RXD1_14") (pintype "output"))
    )
    (net (code "17") (name "/RXD2") (class "Default")
      (node (ref "U12") (pin "13") (pinfunction "RXD2_13") (pintype "output"))
    )
    (net (code "18") (name "/RXD3") (class "Default")
      (node (ref "U12") (pin "10") (pinfunction "RXD3_10") (pintype "output"))
    )
    (net (code "19") (name "/RXD4") (class "Default")
      (node (ref "U12") (pin "11") (pinfunction "RXD4_11") (pintype "output"))
    )
    (net (code "20") (name "/RXD5") (class "Default")
      (node (ref "U12") (pin "8") (pinfunction "RXD5_8") (pintype "output"))
    )
    (net (code "21") (name "/RXD6") (class "Default")
      (node (ref "U12") (pin "9") (pinfunction "RXD6_9") (pintype "output"))
    )
    (net (code "22") (name "/RXD7") (class "Default")
      (node (ref "U12") (pin "6") (pinfunction "RXD7_6") (pintype "output"))
    )
    (net (code "23") (name "/RXD8") (class "Default")
      (node (ref "U12") (pin "5") (pinfunction "RXD8_5") (pintype "output"))
    )
    (net (code "24") (name "/RXD9") (class "Default")
      (node (ref "U12") (pin "4") (pinfunction "RXD9_4") (pintype "output"))
    )
    (net (code "25") (name "/RXD10") (class "Default")
      (node (ref "U12") (pin "3") (pinfunction "RXD10_3") (pintype "output"))
    )
    (net (code "26") (name "/RXD11") (class "Default")
      (node (ref "U12") (pin "2") (pinfunction "RXD11_2") (pintype "output"))
    )
    (net (code "27") (name "/RXIQSEL") (class "Default")
      (node (ref "U12") (pin "16") (pinfunction "RXIQSEL_16") (pintype "output"))
    )
    (net (code "28") (name "/SCL") (class "Default")
      (node (ref "U38") (pin "1") (pinfunction "SCL_1") (pintype "passive"))
    )
    (net (code "29") (name "/SCLK") (class "Default")
      (node (ref "U12") (pin "70") (pinfunction "SCLK_70") (pintype "input"))
    )
    (net (code "30") (name "/SCN") (class "Default")
      (node (ref "C112") (pin "2") (pinfunction "2_2") (pintype "passive"))
      (node (ref "ESD5") (pin "2") (pinfunction "A2_2") (pintype "passive"))
    )
    (net (code "31") (name "/SDA") (class "Default")
      (node (ref "U38") (pin "6") (pinfunction "SDA_6") (pintype "passive"))
    )
    (net (code "32") (name "/SEN") (class "Default")
      (node (ref "U12") (pin "67") (pinfunction "SEN_67") (pintype "input"))
    )
    (net (code "33") (name "/TX") (class "Default")
      (node (ref "C109") (pin "2") (pinfunction "2_2") (pintype "passive"))
      (node (ref "C110") (pin "2") (pinfunction "2_2") (pintype "passive"))
      (node (ref "ESD3") (pin "2") (pinfunction "A2_2") (pintype "passive"))
    )
    (net (code "34") (name "/TXD0") (class "Default")
      (node (ref "U12") (pin "21") (pinfunction "TXD0_21") (pintype "input"))
    )
    (net (code "35") (name "/TXD1") (class "Default")
      (node (ref "U12") (pin "22") (pinfunction "TXD1_22") (pintype "input"))
    )
    (net (code "36") (name "/TXD2") (class "Default")
      (node (ref "U12") (pin "23") (pinfunction "TXD2_23") (pintype "input"))
    )
    (net (code "37") (name "/TXD3") (class "Default")
      (node (ref "U12") (pin "24") (pinfunction "TXD3_24") (pintype "input"))
    )
    (net (code "38") (name "/TXD4") (class "Default")
      (node (ref "U12") (pin "25") (pinfunction "TXD4_25") (pintype "input"))
    )
    (net (code "39") (name "/TXD5") (class "Default")
      (node (ref "U12") (pin "26") (pinfunction "TXD5_26") (pintype "input"))
    )
    (net (code "40") (name "/TXD6") (class "Default")
      (node (ref "U12") (pin "27") (pinfunction "TXD6_27") (pintype "input"))
    )
    (net (code "41") (name "/TXD7") (class "Default")
      (node (ref "U12") (pin "28") (pinfunction "TXD7_28") (pintype "input"))
    )
    (net (code "42") (name "/TXD8") (class "Default")
      (node (ref "U12") (pin "29") (pinfunction "TXD8_29") (pintype "input"))
    )
    (net (code "43") (name "/TXD9") (class "Default")
      (node (ref "U12") (pin "30") (pinfunction "TXD9_30") (pintype "input"))
    )
    (net (code "44") (name "/TXD10") (class "Default")
      (node (ref "U12") (pin "31") (pinfunction "TXD10_31") (pintype "input"))
    )
    (net (code "45") (name "/TXD11") (class "Default")
      (node (ref "U12") (pin "32") (pinfunction "TXD11_32") (pintype "input"))
    )
    (net (code "46") (name "/TXIQSEL") (class "Default")
      (node (ref "U12") (pin "20") (pinfunction "TXIQSEL_20") (pintype "input"))
    )
    (net (code "47") (name "GND") (class "Default")
      (node (ref "C100") (pin "1") (pinfunction "1_1") (pintype "passive"))
      (node (ref "C169") (pin "2") (pinfunction "-_2") (pintype "passive"))
      (node (ref "C301") (pin "2") (pinfunction "2_2") (pintype "passive"))
      (node (ref "C44") (pin "2") (pinfunction "2_2") (pintype "passive"))
      (node (ref "C45") (pin "1") (pinfunction "1_1") (pintype "passive"))
      (node (ref "C48") (pin "2") (pinfunction "2_2") (pintype "passive"))
      (node (ref "C49") (pin "2") (pinfunction "2_2") (pintype "passive"))
      (node (ref "C50") (pin "2") (pinfunction "2_2") (pintype "passive"))
      (node (ref "C51") (pin "2") (pinfunction "-_2") (pintype "passive"))
      (node (ref "C52") (pin "2") (pinfunction "-_2") (pintype "passive"))
      (node (ref "C53") (pin "2") (pinfunction "-_2") (pintype "passive"))
      (node (ref "C54") (pin "2") (pinfunction "-_2") (pintype "passive"))
      (node (ref "C55") (pin "2") (pinfunction "2_2") (pintype "passive"))
      (node (ref "C56") (pin "2") (pinfunction "2_2") (pintype "passive"))
      (node (ref "C57") (pin "2") (pinfunction "2_2") (pintype "passive"))
      (node (ref "C58") (pin "2") (pinfunction "2_2") (pintype "passive"))
      (node (ref "C59") (pin "1") (pinfunction "1_1") (pintype "passive"))
      (node (ref "C60") (pin "1") (pinfunction "1_1") (pintype "passive"))
      (node (ref "C61") (pin "1") (pinfunction "1_1") (pintype "passive"))
      (node (ref "C62") (pin "1") (pinfunction "1_1") (pintype "passive"))
      (node (ref "C63") (pin "1") (pinfunction "1_1") (pintype "passive"))
      (node (ref "C64") (pin "2") (pinfunction "-_2") (pintype "passive"))
      (node (ref "C65") (pin "2") (pinfunction "-_2") (pintype "passive"))
      (node (ref "C66") (pin "2") (pinfunction "-_2") (pintype "passive"))
      (node (ref "C67") (pin "1") (pinfunction "1_1") (pintype "passive"))
      (node (ref "C68") (pin "2") (pinfunction "2_2") (pintype "passive"))
      (node (ref "C69") (pin "2") (pinfunction "2_2") (pintype "passive"))
      (node (ref "C70") (pin "2") (pinfunction "2_2") (pintype "passive"))
      (node (ref "C71") (pin "2") (pinfunction "2_2") (pintype "passive"))
      (node (ref "C72") (pin "2") (pinfunction "2_2") (pintype "passive"))
      (node (ref "C73") (pin "2") (pinfunction "2_2") (pintype "passive"))
      (node (ref "C74") (pin "2") (pinfunction "2_2") (pintype "passive"))
      (node (ref "C75") (pin "2") (pinfunction "2_2") (pintype "passive"))
      (node (ref "C76") (pin "2") (pinfunction "2_2") (pintype "passive"))
      (node (ref "C77") (pin "2") (pinfunction "2_2") (pintype "passive"))
      (node (ref "C78") (pin "2") (pinfunction "2_2") (pintype "passive"))
      (node (ref "C79") (pin "2") (pinfunction "2_2") (pintype "passive"))
      (node (ref "C80") (pin "2") (pinfunction "2_2") (pintype "passive"))
      (node (ref "C81") (pin "2") (pinfunction "2_2") (pintype "passive"))
      (node (ref "C82") (pin "2") (pinfunction "2_2") (pintype "passive"))
      (node (ref "C84") (pin "1") (pinfunction "1_1") (pintype "passive"))
      (node (ref "C85") (pin "1") (pinfunction "1_1") (pintype "passive"))
      (node (ref "C86") (pin "2") (pinfunction "2_2") (pintype "passive"))
      (node (ref "C87") (pin "2") (pinfunction "2_2") (pintype "passive"))
      (node (ref "C88") (pin "2") (pinfunction "2_2") (pintype "passive"))
      (node (ref "C89") (pin "2") (pinfunction "2_2") (pintype "passive"))
      (node (ref "C90") (pin "2") (pinfunction "2_2") (pintype "passive"))
      (node (ref "C91") (pin "2") (pinfunction "2_2") (pintype "passive"))
      (node (ref "C92") (pin "2") (pinfunction "2_2") (pintype "passive"))
      (node (ref "C93") (pin "2") (pinfunction "2_2") (pintype "passive"))
      (node (ref "C94") (pin "1") (pinfunction "1_1") (pintype "passive"))
      (node (ref "C95") (pin "2") (pinfunction "2_2") (pintype "passive"))
      (node (ref "C97") (pin "1") (pinfunction "1_1") (pintype "passive"))
      (node (ref "C98") (pin "2") (pinfunction "2_2") (pintype "passive"))
      (node (ref "ESD3") (pin "1") (pinfunction "A1_1") (pintype "passive"))
      (node (ref "ESD4") (pin "1") (pinfunction "A1_1") (pintype "passive"))
      (node (ref "ESD5") (pin "1") (pinfunction "A1_1") (pintype "passive"))
      (node (ref "R106") (pin "1") (pinfunction "1_1") (pintype "passive"))
      (node (ref "R107") (pin "1") (pinfunction "1_1") (pintype "passive"))
      (node (ref "R108") (pin "1") (pinfunction "1_1") (pintype "passive"))
      (node (ref "R110") (pin "1") (pinfunction "1_1") (pintype "passive"))
      (node (ref "R111") (pin "1") (pinfunction "1_1") (pintype "passive"))
      (node (ref "R112") (pin "1") (pinfunction "1_1") (pintype "passive"))
      (node (ref "R113") (pin "1") (pinfunction "1_1") (pintype "passive"))
      (node (ref "R121") (pin "2") (pinfunction "2_2") (pintype "passive"))
      (node (ref "R96") (pin "1") (pinfunction "1_1") (pintype "passive"))
      (node (ref "R97") (pin "1") (pinfunction "1_1") (pintype "passive"))
      (node (ref "R98") (pin "1") (pinfunction "1_1") (pintype "passive"))
      (node (ref "T1") (pin "6") (pinfunction "Pri_Dot_6") (pintype "passive"))
      (node (ref "T2") (pin "4") (pinfunction "Pri_4") (pintype "passive"))
      (node (ref "T3") (pin "2") (pinfunction "Sec_CT_2") (pintype "passive"))
      (node (ref "T3") (pin "6") (pinfunction "Pri_Dot_6") (pintype "passive"))
      (node (ref "U12") (pin "0") (pinfunction "GND_0") (pintype "power_in"))
      (node (ref "U12") (pin "53") (pinfunction "UNUSED_53") (pintype "passive"))
      (node (ref "U12") (pin "55") (pinfunction "UNUSED_55") (pintype "passive"))
      (node (ref "U12") (pin "88") (pinfunction "UNUSED_88") (pintype "passive"))
      (node (ref "U12") (pin "93") (pinfunction "UNUSED_93") (pintype "passive"))
      (node (ref "U12") (pin "97") (pinfunction "RXIN1EP_97") (pintype "bidirectional"))
      (node (ref "U12") (pin "99") (pinfunction "RXIN1EN_99") (pintype "bidirectional"))
      (node (ref "U14") (pin "2") (pinfunction "GND_2") (pintype "power_in"))
      (node (ref "U14") (pin "4") (pinfunction "GND_4") (pintype "power_in"))
      (node (ref "U38") (pin "2") (pinfunction "GND_2") (pintype "passive"))
      (node (ref "Z1") (pin "2") (pinfunction "2_2") (pintype "passive"))
    )
    (net (code "48") (name "Net-(C48-Pad1)") (class "Default")
      (node (ref "C48") (pin "1") (pinfunction "1_1") (pintype "passive"))
      (node (ref "C49") (pin "1") (pinfunction "1_1") (pintype "passive"))
      (node (ref "C50") (pin "1") (pinfunction "1_1") (pintype "passive"))
      (node (ref "L10") (pin "1") (pinfunction "1_1") (pintype "passive"))
      (node (ref "L8") (pin "1") (pinfunction "1_1") (pintype "passive"))
      (node (ref "L9") (pin "1") (pinfunction "1_1") (pintype "passive"))
      (node (ref "Z1") (pin "3") (pinfunction "3_3") (pintype "passive"))
    )
    (net (code "49") (name "Net-(C52-+)") (class "Default")
      (node (ref "C52") (pin "1") (pinfunction "+_1") (pintype "passive"))
      (node (ref "C56") (pin "1") (pinfunction "1_1") (pintype "passive"))
      (node (ref "L8") (pin "2") (pinfunction "2_2") (pintype "passive"))
      (node (ref "U30") (pin "3") (pinfunction "Vin_3") (pintype "passive"))
    )
    (net (code "50") (name "Net-(C53-+)") (class "Default")
      (node (ref "C53") (pin "1") (pinfunction "+_1") (pintype "passive"))
      (node (ref "C57") (pin "1") (pinfunction "1_1") (pintype "passive"))
      (node (ref "L9") (pin "2") (pinfunction "2_2") (pintype "passive"))
      (node (ref "U31") (pin "3") (pinfunction "Vin_3") (pintype "passive"))
    )
    (net (code "51") (name "Net-(C54-+)") (class "Default")
      (node (ref "C54") (pin "1") (pinfunction "+_1") (pintype "passive"))
      (node (ref "C58") (pin "1") (pinfunction "1_1") (pintype "passive"))
      (node (ref "L10") (pin "2") (pinfunction "2_2") (pintype "passive"))
      (node (ref "U32") (pin "3") (pinfunction "Vin_3") (pintype "passive"))
    )
    (net (code "52") (name "Net-(C60-Pad2)") (class "Default")
      (node (ref "C60") (pin "2") (pinfunction "2_2") (pintype "passive"))
      (node (ref "L18") (pin "1") (pinfunction "1_1") (pintype "passive"))
      (node (ref "R104") (pin "1") (pinfunction "1_1") (pintype "passive"))
      (node (ref "R105") (pin "1") (pinfunction "1_1") (pintype "passive"))
    )
    (net (code "53") (name "Net-(C83-Pad2)") (class "Default")
      (node (ref "C83") (pin "2") (pinfunction "2_2") (pintype "passive"))
      (node (ref "R106") (pin "2") (pinfunction "2_2") (pintype "passive"))
    )
    (net (code "54") (name "Net-(C94-Pad2)") (class "Default")
      (node (ref "C94") (pin "2") (pinfunction "2_2") (pintype "passive"))
      (node (ref "C95") (pin "1") (pinfunction "1_1") (pintype "passive"))
      (node (ref "L29") (pin "1") (pinfunction "1_1") (pintype "passive"))
      (node (ref "L30") (pin "1") (pinfunction "1_1") (pintype "passive"))
      (node (ref "L31") (pin "1") (pinfunction "1_1") (pintype "passive"))
    )
    (net (code "55") (name "Net-(C99-Pad2)") (class "Default")
      (node (ref "C99") (pin "2") (pinfunction "2_2") (pintype "passive"))
      (node (ref "R121") (pin "1") (pinfunction "1_1") (pintype "passive"))
    )
    (net (code "56") (name "Net-(C102-Pad2)") (class "Default")
      (node (ref "C102") (pin "2") (pinfunction "2_2") (pintype "passive"))
      (node (ref "L32") (pin "1") (pinfunction "1_1") (pintype "passive"))
    )
    (net (code "57") (name "Net-(C103-Pad2)") (class "Default")
      (node (ref "C103") (pin "2") (pinfunction "2_2") (pintype "passive"))
      (node (ref "L33") (pin "1") (pinfunction "1_1") (pintype "passive"))
    )
    (net (code "58") (name "Net-(C108-Pad2)") (class "Default")
      (node (ref "C108") (pin "2") (pinfunction "2_2") (pintype "passive"))
      (node (ref "C109") (pin "1") (pinfunction "1_1") (pintype "passive"))
    )
    (net (code "59") (name "Net-(C146-Pad1)") (class "Default")
      (node (ref "C146") (pin "1") (pinfunction "1_1") (pintype "passive"))
      (node (ref "C45") (pin "2") (pinfunction "2_2") (pintype "passive"))
      (node (ref "R177") (pin "2") (pinfunction "2_2") (pintype "passive"))
    )
    (net (code "60") (name "Net-(R107-Pad2)") (class "Default")
      (node (ref "R107") (pin "2") (pinfunction "2_2") (pintype "passive"))
      (node (ref "R114") (pin "1") (pinfunction "1_1") (pintype "passive"))
    )
    (net (code "61") (name "Net-(T1-Pri)") (class "Default")
      (node (ref "C101") (pin "1") (pinfunction "1_1") (pintype "passive"))
      (node (ref "C108") (pin "1") (pinfunction "1_1") (pintype "passive"))
      (node (ref "T1") (pin "4") (pinfunction "Pri_4") (pintype "passive"))
    )
    (net (code "62") (name "Net-(T1-Sec)") (class "Default")
      (node (ref "C105") (pin "2") (pinfunction "2_2") (pintype "passive"))
      (node (ref "C96'") (pin "1") (pinfunction "1_1") (pintype "passive"))
      (node (ref "T1") (pin "1") (pinfunction "Sec_1") (pintype "passive"))
    )
    (net (code "63") (name "Net-(T1-Sec_Dot)") (class "Default")
      (node (ref "C104") (pin "2") (pinfunction "2_2") (pintype "passive"))
      (node (ref "C96'") (pin "2") (pinfunction "2_2") (pintype "passive"))
      (node (ref "T1") (pin "3") (pinfunction "Sec_Dot_3") (pintype "passive"))
    )
    (net (code "64") (name "Net-(T2-Pri_Dot)") (class "Default")
      (node (ref "C111") (pin "2") (pinfunction "2_2") (pintype "passive"))
      (node (ref "T2") (pin "6") (pinfunction "Pri_Dot_6") (pintype "passive"))
    )
    (net (code "65") (name "Net-(T2-Sec)") (class "Default")
      (node (ref "C106") (pin "2") (pinfunction "2_2") (pintype "passive"))
      (node (ref "T2") (pin "1") (pinfunction "Sec_1") (pintype "passive"))
    )
    (net (code "66") (name "Net-(T2-Sec_Dot)") (class "Default")
      (node (ref "C107") (pin "2") (pinfunction "2_2") (pintype "passive"))
      (node (ref "T2") (pin "3") (pinfunction "Sec_Dot_3") (pintype "passive"))
    )
    (net (code "67") (name "Net-(T3-Pri)") (class "Default")
      (node (ref "C112") (pin "1") (pinfunction "1_1") (pintype "passive"))
      (node (ref "T3") (pin "4") (pinfunction "Pri_4") (pintype "passive"))
    )
    (net (code "68") (name "Net-(T3-Sec)") (class "Default")
      (node (ref "L32") (pin "2") (pinfunction "2_2") (pintype "passive"))
      (node (ref "T3") (pin "1") (pinfunction "Sec_1") (pintype "passive"))
    )
    (net (code "69") (name "Net-(T3-Sec_Dot)") (class "Default")
      (node (ref "L33") (pin "2") (pinfunction "2_2") (pintype "passive"))
      (node (ref "T3") (pin "3") (pinfunction "Sec_Dot_3") (pintype "passive"))
    )
    (net (code "70") (name "Net-(U12A-PVDDAD33A)") (class "Default")
      (node (ref "C81") (pin "1") (pinfunction "1_1") (pintype "passive"))
      (node (ref "U12") (pin "1") (pinfunction "PVDDAD33A_1") (pintype "power_in"))
    )
    (net (code "71") (name "Net-(U12A-PVDDAD33D)") (class "Default")
      (node (ref "C77") (pin "1") (pinfunction "1_1") (pintype "passive"))
      (node (ref "R103") (pin "2") (pinfunction "2_2") (pintype "passive"))
      (node (ref "U12") (pin "34") (pinfunction "PVDDAD33D_34") (pintype "power_in"))
    )
    (net (code "72") (name "Net-(U12A-PVDDSPI33)") (class "Default")
      (node (ref "C80") (pin "1") (pinfunction "1_1") (pintype "passive"))
      (node (ref "L13") (pin "2") (pinfunction "2_2") (pintype "passive"))
      (node (ref "U12") (pin "74") (pinfunction "PVDDSPI33_74") (pintype "power_in"))
    )
    (net (code "73") (name "Net-(U12A-PVDDVGG)") (class "Default")
      (node (ref "C76") (pin "1") (pinfunction "1_1") (pintype "passive"))
      (node (ref "L17") (pin "2") (pinfunction "2_2") (pintype "passive"))
      (node (ref "U12") (pin "7") (pinfunction "PVDDVGG_7") (pintype "power_in"))
    )
    (net (code "74") (name "Net-(U12A-RAVDD18)") (class "Default")
      (node (ref "C62") (pin "2") (pinfunction "2_2") (pintype "passive"))
      (node (ref "L11") (pin "1") (pinfunction "1_1") (pintype "passive"))
      (node (ref "U12") (pin "35") (pinfunction "RAVDD18_35") (pintype "power_in"))
    )
    (net (code "75") (name "Net-(U12A-RDVDD18)") (class "Default")
      (node (ref "C63") (pin "2") (pinfunction "2_2") (pintype "passive"))
      (node (ref "L20") (pin "1") (pinfunction "1_1") (pintype "passive"))
      (node (ref "U12") (pin "33") (pinfunction "RDVDD18_33") (pintype "power_in"))
      (node (ref "U12") (pin "36") (pinfunction "TDVDD18_36") (pintype "power_in"))
    )
    (net (code "76") (name "Net-(U12A-RXPVDD33)") (class "Default")
      (node (ref "C88") (pin "1") (pinfunction "1_1") (pintype "passive"))
      (node (ref "L23") (pin "1") (pinfunction "1_1") (pintype "passive"))
      (node (ref "U12") (pin "107") (pinfunction "RXPVDD33_107") (pintype "power_in"))
      (node (ref "U12") (pin "109") (pinfunction "RXVCCTIA33_109") (pintype "power_in"))
    )
    (net (code "77") (name "Net-(U12A-RXPVDDPLL33A)") (class "Default")
      (node (ref "C93") (pin "1") (pinfunction "1_1") (pintype "passive"))
      (node (ref "L28") (pin "2") (pinfunction "2_2") (pintype "passive"))
      (node (ref "U12") (pin "86") (pinfunction "RXPVDDPLL33A_86") (pintype "power_in"))
    )
    (net (code "78") (name "Net-(U12A-RXPVDDPLL33B)") (class "Default")
      (node (ref "C91") (pin "1") (pinfunction "1_1") (pintype "passive"))
      (node (ref "L26") (pin "2") (pinfunction "2_2") (pintype "passive"))
      (node (ref "U12") (pin "78") (pinfunction "RXVCCCHP33_78") (pintype "power_in"))
      (node (ref "U12") (pin "79") (pinfunction "RXVCCLOB33_79") (pintype "power_in"))
      (node (ref "U12") (pin "81") (pinfunction "RXPVDDPLL33B_81") (pintype "power_in"))
      (node (ref "U12") (pin "82") (pinfunction "RXVCCVCO33_82") (pintype "power_in"))
      (node (ref "U12") (pin "85") (pinfunction "RXVCCPLL33_85") (pintype "power_in"))
    )
    (net (code "79") (name "Net-(U12A-RXVCCLNA33)") (class "Default")
      (node (ref "C90") (pin "1") (pinfunction "1_1") (pintype "passive"))
      (node (ref "L25") (pin "1") (pinfunction "1_1") (pintype "passive"))
      (node (ref "U12") (pin "101") (pinfunction "RXVCCLNA33_101") (pintype "power_in"))
      (node (ref "U12") (pin "90") (pinfunction "RXVCCMIX33_90") (pintype "power_in"))
    )
    (net (code "80") (name "Net-(U12A-RXVCCLPF33)") (class "Default")
      (node (ref "C86") (pin "1") (pinfunction "1_1") (pintype "passive"))
      (node (ref "L21") (pin "1") (pinfunction "1_1") (pintype "passive"))
      (node (ref "U12") (pin "111") (pinfunction "RXVCCLPF33_111") (pintype "power_in"))
      (node (ref "U12") (pin "112") (pinfunction "RXVCCVGA33_112") (pintype "power_in"))
    )
    (net (code "81") (name "Net-(U12A-RXVCCPLL18)") (class "Default")
      (node (ref "C61") (pin "2") (pinfunction "2_2") (pintype "passive"))
      (node (ref "L16") (pin "1") (pinfunction "1_1") (pintype "passive"))
      (node (ref "U12") (pin "83") (pinfunction "RXVCCPLL18_83") (pintype "power_in"))
    )
    (net (code "82") (name "Net-(U12A-RXVDDVCO18)") (class "Default")
      (node (ref "C75") (pin "1") (pinfunction "1_1") (pintype "passive"))
      (node (ref "C79") (pin "1") (pinfunction "1_1") (pintype "passive"))
      (node (ref "L15") (pin "2") (pinfunction "2_2") (pintype "passive"))
      (node (ref "U12") (pin "84") (pinfunction "RXVDDVCO18_84") (pintype "power_in"))
    )
    (net (code "83") (name "Net-(U12A-TAVDD33)") (class "Default")
      (node (ref "C74") (pin "1") (pinfunction "1_1") (pintype "passive"))
      (node (ref "L12") (pin "2") (pinfunction "2_2") (pintype "passive"))
      (node (ref "U12") (pin "37") (pinfunction "TAVDD33_37") (pintype "power_in"))
    )
    (net (code "84") (name "Net-(U12A-TRXVDDDSM18)") (class "Default")
      (node (ref "R104") (pin "2") (pinfunction "2_2") (pintype "passive"))
      (node (ref "U12") (pin "72") (pinfunction "TRXVDDDSM18_72") (pintype "power_in"))
    )
    (net (code "85") (name "Net-(U12A-TXPVDD33)") (class "Default")
      (node (ref "C92") (pin "1") (pinfunction "1_1") (pintype "passive"))
      (node (ref "L27") (pin "1") (pinfunction "1_1") (pintype "passive"))
      (node (ref "U12") (pin "43") (pinfunction "TXVCCLPF33_43") (pintype "power_in"))
      (node (ref "U12") (pin "45") (pinfunction "TXVCCMIX33_45") (pintype "power_in"))
      (node (ref "U12") (pin "47") (pinfunction "TXPVDD33_47") (pintype "power_in"))
      (node (ref "U12") (pin "49") (pinfunction "TXVCCDRV33_49") (pintype "power_in"))
    )
    (net (code "86") (name "Net-(U12A-TXPVDDPLL33A)") (class "Default")
      (node (ref "C87") (pin "1") (pinfunction "1_1") (pintype "passive"))
      (node (ref "L22") (pin "2") (pinfunction "2_2") (pintype "passive"))
      (node (ref "U12") (pin "58") (pinfunction "TXPVDDPLL33A_58") (pintype "power_in"))
    )
    (net (code "87") (name "Net-(U12A-TXPVDDPLL33B)") (class "Default")
      (node (ref "C89") (pin "1") (pinfunction "1_1") (pintype "passive"))
      (node (ref "L24") (pin "2") (pinfunction "2_2") (pintype "passive"))
      (node (ref "U12") (pin "59") (pinfunction "TXVCCVCO33_59") (pintype "power_in"))
      (node (ref "U12") (pin "62") (pinfunction "TXPVDDPLL33B_62") (pintype "power_in"))
      (node (ref "U12") (pin "63") (pinfunction "TXVCCHP33_63") (pintype "power_in"))
    )
    (net (code "88") (name "Net-(U12A-TXVCCPLL18)") (class "Default")
      (node (ref "C59") (pin "2") (pinfunction "2_2") (pintype "passive"))
      (node (ref "L19") (pin "1") (pinfunction "1_1") (pintype "passive"))
      (node (ref "U12") (pin "61") (pinfunction "TXVCCPLL18_61") (pintype "power_in"))
    )
    (net (code "89") (name "Net-(U12A-TXVDDVCO18)") (class "Default")
      (node (ref "C73") (pin "1") (pinfunction "1_1") (pintype "passive"))
      (node (ref "C78") (pin "1") (pinfunction "1_1") (pintype "passive"))
      (node (ref "L14") (pin "2") (pinfunction "2_2") (pintype "passive"))
      (node (ref "U12") (pin "60") (pinfunction "TXVDDVCO18_60") (pintype "power_in"))
    )
    (net (code "90") (name "Net-(U12A-VSPI18)") (class "Default")
      (node (ref "R105") (pin "2") (pinfunction "2_2") (pintype "passive"))
      (node (ref "U12") (pin "73") (pinfunction "VSPI18_73") (pintype "power_in"))
    )
    (net (code "91") (name "Net-(U12B-PLLCLK)") (class "Default")
      (node (ref "C146") (pin "2") (pinfunction "2_2") (pintype "passive"))
      (node (ref "U12") (pin "71") (pinfunction "PLLCLK_71") (pintype "input"))
    )
    (net (code "92") (name "Net-(U12B-PLLCLK_OUT)") (class "Default")
      (node (ref "TST3") (pin "1") (pinfunction "1_1") (pintype "passive"))
      (node (ref "U12") (pin "41") (pinfunction "PLLCLK_OUT_41") (pintype "output"))
    )
    (net (code "93") (name "Net-(U12B-RXCLK)") (class "Default")
      (node (ref "R80") (pin "2") (pinfunction "2_2") (pintype "passive"))
      (node (ref "U12") (pin "17") (pinfunction "RXCLK_17") (pintype "input"))
      (node (ref "U12") (pin "19") (pinfunction "TXCLK_19") (pintype "input"))
    )
    (net (code "94") (name "Net-(U12B-TSTD_OUT1)") (class "Default")
      (node (ref "TST1") (pin "1") (pinfunction "1_1") (pintype "passive"))
      (node (ref "U12") (pin "65") (pinfunction "TSTD_OUT1_65") (pintype "output"))
    )
    (net (code "95") (name "Net-(U12B-TSTD_OUT2)") (class "Default")
      (node (ref "TST2") (pin "1") (pinfunction "1_1") (pintype "passive"))
      (node (ref "U12") (pin "77") (pinfunction "TSTD_OUT2_77") (pintype "output"))
    )
    (net (code "96") (name "Net-(U12C-AUXIN{slash}ATPOUT)") (class "Default")
      (node (ref "TST4") (pin "1") (pinfunction "1_1") (pintype "passive"))
      (node (ref "U12") (pin "42") (pinfunction "AUXIN/ATPOUT_42") (pintype "bidirectional"))
    )
    (net (code "97") (name "Net-(U12C-RXCPOUT)") (class "Default")
      (node (ref "C98") (pin "1") (pinfunction "1_1") (pintype "passive"))
      (node (ref "C99") (pin "1") (pinfunction "1_1") (pintype "passive"))
      (node (ref "R119") (pin "2") (pinfunction "2_2") (pintype "passive"))
      (node (ref "U12") (pin "80") (pinfunction "RXCPOUT_80") (pintype "output"))
    )
    (net (code "98") (name "Net-(U12C-RXOUTIN)") (class "Default")
      (node (ref "TST6") (pin "1") (pinfunction "1_1") (pintype "passive"))
      (node (ref "U12") (pin "115") (pinfunction "RXOUTIN_115") (pintype "output"))
    )
    (net (code "99") (name "Net-(U12C-RXOUTIP)") (class "Default")
      (node (ref "TST5") (pin "1") (pinfunction "1_1") (pintype "passive"))
      (node (ref "U12") (pin "116") (pinfunction "RXOUTIP_116") (pintype "output"))
    )
    (net (code "100") (name "Net-(U12C-RXOUTQN)") (class "Default")
      (node (ref "TST8") (pin "1") (pinfunction "1_1") (pintype "passive"))
      (node (ref "U12") (pin "114") (pinfunction "RXOUTQN_114") (pintype "output"))
    )
    (net (code "101") (name "Net-(U12C-RXOUTQP)") (class "Default")
      (node (ref "TST7") (pin "1") (pinfunction "1_1") (pintype "passive"))
      (node (ref "U12") (pin "113") (pinfunction "RXOUTQP_113") (pintype "output"))
    )
    (net (code "102") (name "Net-(U12C-RXVTUNE)") (class "Default")
      (node (ref "C97") (pin "2") (pinfunction "2_2") (pintype "passive"))
      (node (ref "R119") (pin "1") (pinfunction "1_1") (pintype "passive"))
      (node (ref "U12") (pin "87") (pinfunction "RXVTUNE_87") (pintype "input"))
    )
    (net (code "103") (name "Net-(U12C-TXCPOUT)") (class "Default")
      (node (ref "C82") (pin "1") (pinfunction "1_1") (pintype "passive"))
      (node (ref "C83") (pin "1") (pinfunction "1_1") (pintype "passive"))
      (node (ref "R109") (pin "1") (pinfunction "1_1") (pintype "passive"))
      (node (ref "U12") (pin "64") (pinfunction "TXCPOUT_64") (pintype "output"))
    )
    (net (code "104") (name "Net-(U12C-TXININ)") (class "Default")
      (node (ref "R111") (pin "2") (pinfunction "2_2") (pintype "passive"))
      (node (ref "U12") (pin "51") (pinfunction "TXININ_51") (pintype "input"))
    )
    (net (code "105") (name "Net-(U12C-TXINIP)") (class "Default")
      (node (ref "R110") (pin "2") (pinfunction "2_2") (pintype "passive"))
      (node (ref "U12") (pin "52") (pinfunction "TXINIP_52") (pintype "input"))
    )
    (net (code "106") (name "Net-(U12C-TXINQN)") (class "Default")
      (node (ref "R113") (pin "2") (pinfunction "2_2") (pintype "passive"))
      (node (ref "U12") (pin "56") (pinfunction "TXINQN_56") (pintype "input"))
    )
    (net (code "107") (name "Net-(U12C-TXINQP)") (class "Default")
      (node (ref "R112") (pin "2") (pinfunction "2_2") (pintype "passive"))
      (node (ref "U12") (pin "54") (pinfunction "TXINQP_54") (pintype "input"))
    )
    (net (code "108") (name "Net-(U12C-TXVTUNE)") (class "Default")
      (node (ref "C84") (pin "2") (pinfunction "2_2") (pintype "passive"))
      (node (ref "R109") (pin "2") (pinfunction "2_2") (pintype "passive"))
      (node (ref "U12") (pin "57") (pinfunction "TXVTUNE_57") (pintype "input"))
    )
    (net (code "109") (name "Net-(U12C-VREFAD)") (class "Default")
      (node (ref "C85") (pin "2") (pinfunction "2_2") (pintype "passive"))
      (node (ref "U12") (pin "38") (pinfunction "VREFAD_38") (pintype "bidirectional"))
    )
    (net (code "110") (name "Net-(U12C-XRES12k)") (class "Default")
      (node (ref "R108") (pin "2") (pinfunction "2_2") (pintype "passive"))
      (node (ref "U12") (pin "89") (pinfunction "XRES12k_89") (pintype "bidirectional"))
    )
    (net (code "111") (name "Net-(U12C-XRESAD)") (class "Default")
      (node (ref "R114") (pin "2") (pinfunction "2_2") (pintype "passive"))
      (node (ref "U12") (pin "39") (pinfunction "XRESAD_39") (pintype "bidirectional"))
    )
    (net (code "112") (name "Net-(U12D-RXIN1N)") (class "Default")
      (node (ref "C107") (pin "1") (pinfunction "1_1") (pintype "passive"))
      (node (ref "U12") (pin "98") (pinfunction "RXIN1N_98") (pintype "input"))
    )
    (net (code "113") (name "Net-(U12D-RXIN1P)") (class "Default")
      (node (ref "C106") (pin "1") (pinfunction "1_1") (pintype "passive"))
      (node (ref "U12") (pin "96") (pinfunction "RXIN1P_96") (pintype "input"))
    )
    (net (code "114") (name "Net-(U12D-RXIN2N)") (class "Default")
      (node (ref "R125") (pin "2") (pinfunction "2_2") (pintype "passive"))
      (node (ref "U12") (pin "102") (pinfunction "RXIN2N_102") (pintype "input"))
    )
    (net (code "115") (name "Net-(U12D-RXIN2P)") (class "Default")
      (node (ref "R125") (pin "1") (pinfunction "1_1") (pintype "passive"))
      (node (ref "U12") (pin "100") (pinfunction "RXIN2P_100") (pintype "input"))
    )
    (net (code "116") (name "Net-(U12D-RXIN3N)") (class "Default")
      (node (ref "C103") (pin "1") (pinfunction "1_1") (pintype "passive"))
      (node (ref "U12") (pin "110") (pinfunction "RXIN3N_110") (pintype "input"))
    )
    (net (code "117") (name "Net-(U12D-RXIN3P)") (class "Default")
      (node (ref "C102") (pin "1") (pinfunction "1_1") (pintype "passive"))
      (node (ref "U12") (pin "108") (pinfunction "RXIN3P_108") (pintype "input"))
    )
    (net (code "118") (name "Net-(U12D-TXOUT2N)") (class "Default")
      (node (ref "C105") (pin "1") (pinfunction "1_1") (pintype "passive"))
      (node (ref "C96") (pin "1") (pinfunction "1_1") (pintype "passive"))
      (node (ref "L31") (pin "2") (pinfunction "2_2") (pintype "passive"))
      (node (ref "U12") (pin "46") (pinfunction "TXOUT2N_46") (pintype "output"))
    )
    (net (code "119") (name "Net-(U12D-TXOUT2P)") (class "Default")
      (node (ref "C104") (pin "1") (pinfunction "1_1") (pintype "passive"))
      (node (ref "C96") (pin "2") (pinfunction "2_2") (pintype "passive"))
      (node (ref "L30") (pin "2") (pinfunction "2_2") (pintype "passive"))
      (node (ref "U12") (pin "44") (pinfunction "TXOUT2P_44") (pintype "output"))
    )
    (net (code "120") (name "Net-(U14-IN)") (class "Default")
      (node (ref "C101") (pin "2") (pinfunction "2_2") (pintype "passive"))
      (node (ref "U14") (pin "3") (pinfunction "IN_3") (pintype "passive"))
    )
    (net (code "121") (name "Net-(U14-OUT)") (class "Default")
      (node (ref "C110") (pin "1") (pinfunction "1_1") (pintype "passive"))
      (node (ref "L34") (pin "2") (pinfunction "2_2") (pintype "passive"))
      (node (ref "U14") (pin "1") (pinfunction "OUT_1") (pintype "passive"))
    )
    (net (code "122") (name "Net-(U30-ADJ)") (class "Default")
      (node (ref "R96") (pin "2") (pinfunction "2_2") (pintype "passive"))
      (node (ref "R99") (pin "1") (pinfunction "1_1") (pintype "passive"))
      (node (ref "U30") (pin "1") (pinfunction "ADJ_1") (pintype "passive"))
    )
    (net (code "123") (name "Net-(U31-ADJ)") (class "Default")
      (node (ref "R100") (pin "1") (pinfunction "1_1") (pintype "passive"))
      (node (ref "R97") (pin "2") (pinfunction "2_2") (pintype "passive"))
      (node (ref "U31") (pin "1") (pinfunction "ADJ_1") (pintype "passive"))
    )
    (net (code "124") (name "Net-(U32-ADJ)") (class "Default")
      (node (ref "R101") (pin "1") (pinfunction "1_1") (pintype "passive"))
      (node (ref "R98") (pin "2") (pinfunction "2_2") (pintype "passive"))
      (node (ref "U32") (pin "1") (pinfunction "ADJ_1") (pintype "passive"))
    )
    (net (code "125") (name "Net-(U38-Vcc)") (class "Default")
      (node (ref "C301") (pin "1") (pinfunction "1_1") (pintype "passive"))
      (node (ref "R176") (pin "2") (pinfunction "2_2") (pintype "passive"))
      (node (ref "U38") (pin "5") (pinfunction "Vcc_5") (pintype "passive"))
    )
    (net (code "126") (name "unconnected-(U12A-PVDDAD33B-Pad12)") (class "Default")
      (node (ref "U12") (pin "12") (pinfunction "PVDDAD33B_12") (pintype "power_in+no_connect"))
    )
    (net (code "127") (name "unconnected-(U12A-PVDDAD33C-Pad18)") (class "Default")
      (node (ref "U12") (pin "18") (pinfunction "PVDDAD33C_18") (pintype "power_in+no_connect"))
    )
    (net (code "128") (name "unconnected-(U12B-RXCLK_OUT-Pad40)") (class "Default")
      (node (ref "U12") (pin "40") (pinfunction "RXCLK_OUT_40") (pintype "output+no_connect"))
    )
    (net (code "129") (name "unconnected-(U12D-IEXMIX1N-Pad94)") (class "Default")
      (node (ref "U12") (pin "94") (pinfunction "IEXMIX1N_94") (pintype "bidirectional+no_connect"))
    )
    (net (code "130") (name "unconnected-(U12D-IEXMIX1P-Pad92)") (class "Default")
      (node (ref "U12") (pin "92") (pinfunction "IEXMIX1P_92") (pintype "bidirectional+no_connect"))
    )
    (net (code "131") (name "unconnected-(U12D-IEXMIX2N-Pad106)") (class "Default")
      (node (ref "U12") (pin "106") (pinfunction "IEXMIX2N_106") (pintype "bidirectional+no_connect"))
    )
    (net (code "132") (name "unconnected-(U12D-IEXMIX2P-Pad104)") (class "Default")
      (node (ref "U12") (pin "104") (pinfunction "IEXMIX2P_104") (pintype "bidirectional+no_connect"))
    )
    (net (code "133") (name "unconnected-(U12D-OEXLNA1N-Pad95)") (class "Default")
      (node (ref "U12") (pin "95") (pinfunction "OEXLNA1N_95") (pintype "bidirectional+no_connect"))
    )
    (net (code "134") (name "unconnected-(U12D-OEXLNA1P-Pad91)") (class "Default")
      (node (ref "U12") (pin "91") (pinfunction "OEXLNA1P_91") (pintype "bidirectional+no_connect"))
    )
    (net (code "135") (name "unconnected-(U12D-OEXLNA2N-Pad105)") (class "Default")
      (node (ref "U12") (pin "105") (pinfunction "OEXLNA2N_105") (pintype "bidirectional+no_connect"))
    )
    (net (code "136") (name "unconnected-(U12D-OEXLNA2P-Pad103)") (class "Default")
      (node (ref "U12") (pin "103") (pinfunction "OEXLNA2P_103") (pintype "bidirectional+no_connect"))
    )
    (net (code "137") (name "unconnected-(U12D-TXOUT1N-Pad50)") (class "Default")
      (node (ref "U12") (pin "50") (pinfunction "TXOUT1N_50") (pintype "output+no_connect"))
    )
    (net (code "138") (name "unconnected-(U12D-TXOUT1P-Pad48)") (class "Default")
      (node (ref "U12") (pin "48") (pinfunction "TXOUT1P_48") (pintype "output+no_connect"))
    )
    (net (code "139") (name "unconnected-(U38-ALRT-Pad3)") (class "Default")
      (node (ref "U38") (pin "3") (pinfunction "ALRT_3") (pintype "passive+no_connect"))
    )
  )
)
